# working.net
KiCad netlist of a schematic drawn in EAGLE
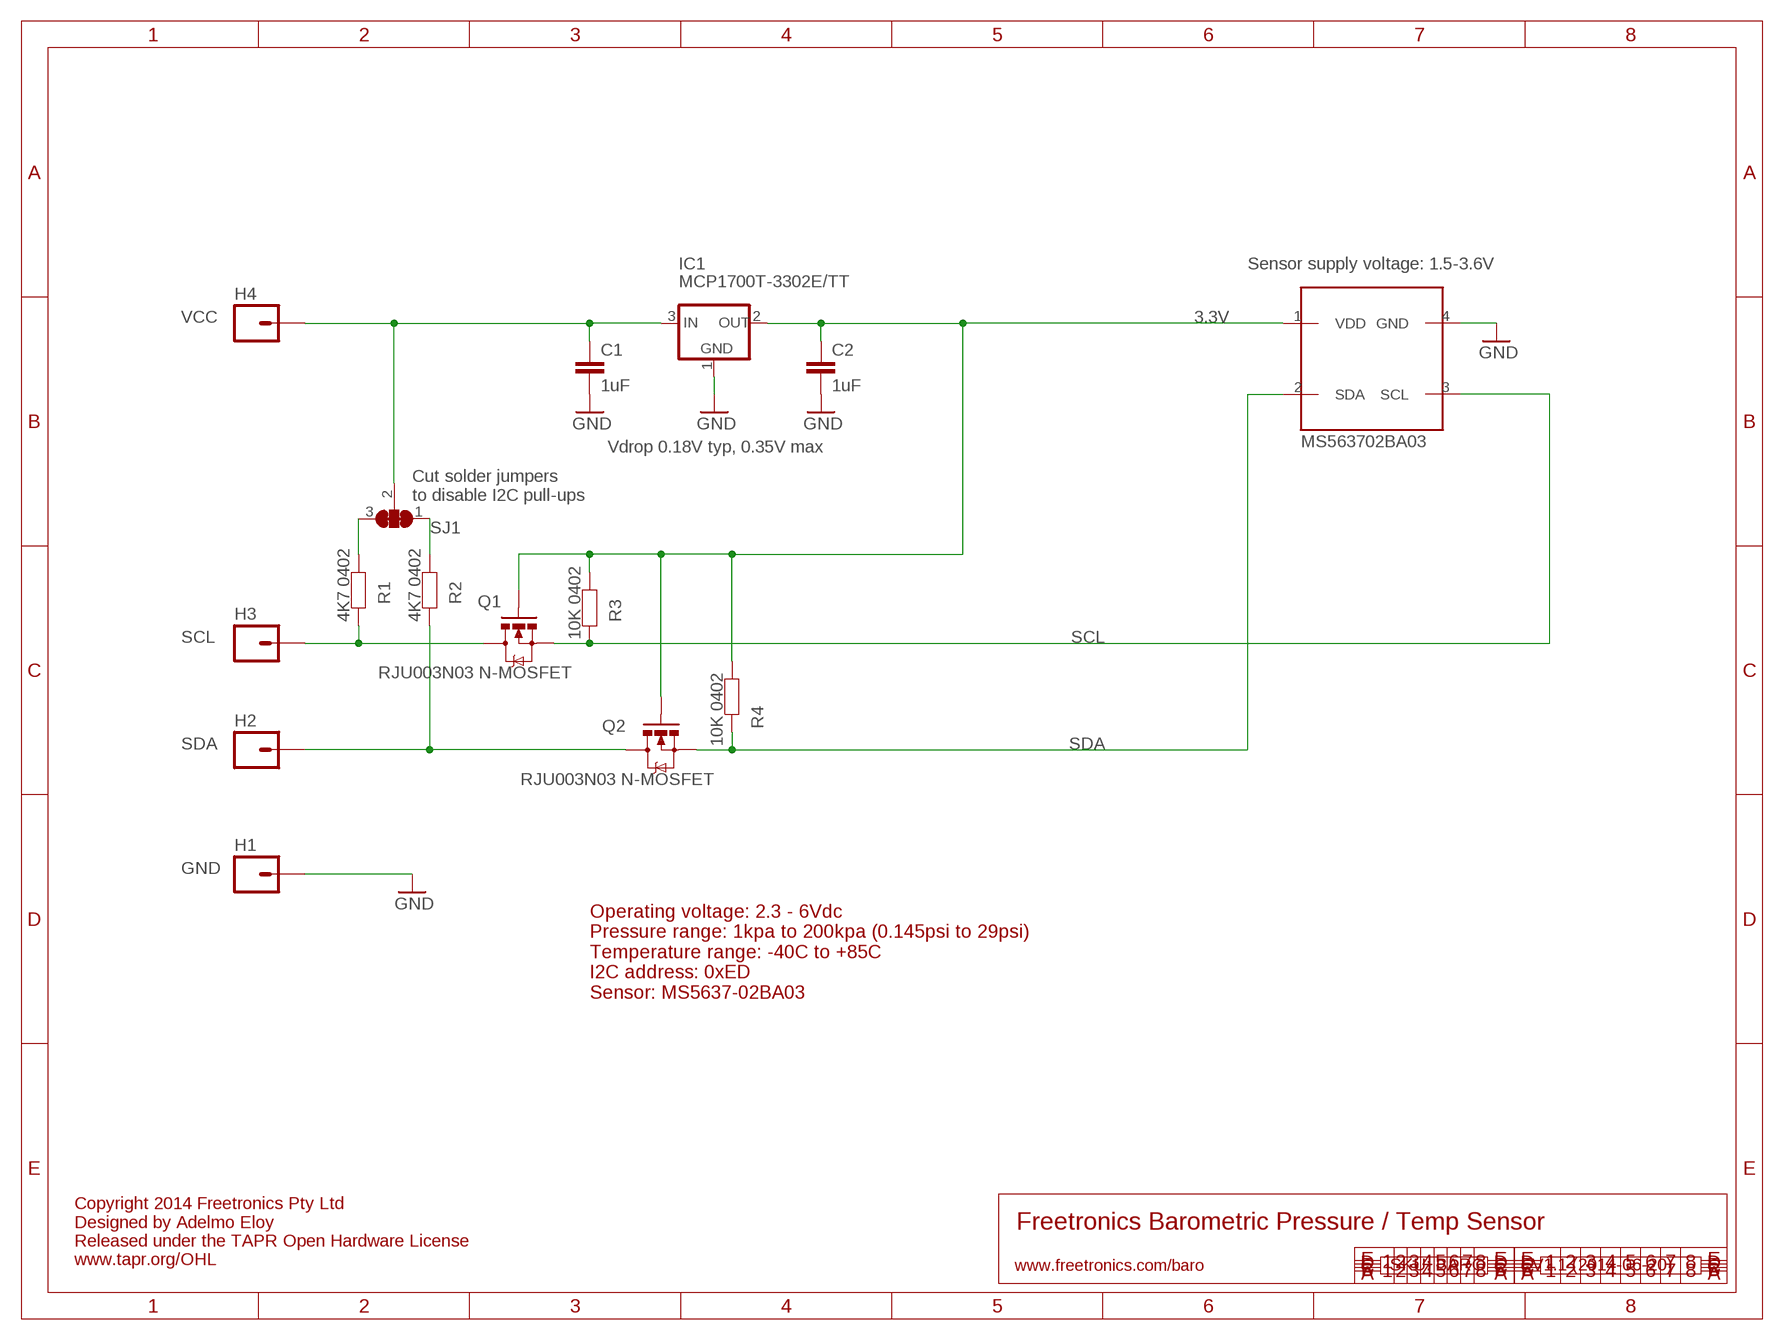
[diagram p0: schematic, sheet 1]

(export (version "E")
  (design (tool "Eeschema 10.0.6"))
  (components
    (comp (ref "C1")
      (value "1uF")
      (footprint "eagle-import:0603")
      (libsource (lib "eagle-import") (part "CAP0603"))
    )
    (comp (ref "C2")
      (value "1uF")
      (footprint "eagle-import:0603")
      (libsource (lib "eagle-import") (part "CAP0603"))
    )
    (comp (ref "H1")
      (value "GND")
      (footprint "eagle-import:1X01")
      (libsource (lib "eagle-import") (part "M01PTH"))
    )
    (comp (ref "H2")
      (value "SDA")
      (footprint "eagle-import:1X01")
      (libsource (lib "eagle-import") (part "M01PTH"))
    )
    (comp (ref "H3")
      (value "SCL")
      (footprint "eagle-import:1X01")
      (libsource (lib "eagle-import") (part "M01PTH"))
    )
    (comp (ref "H4")
      (value "VCC")
      (footprint "eagle-import:1X01")
      (libsource (lib "eagle-import") (part "M01PTH"))
    )
    (comp (ref "IC1")
      (value "MCP1700T-3302E/TT")
      (footprint "eagle-import:SOT23-3")
      (libsource (lib "eagle-import") (part "V_REG_78XXSOT23-3"))
    )
    (comp (ref "IC2")
      (value "MS563702BA03")
      (footprint "eagle-import:MS5637")
      (libsource (lib "eagle-import") (part "MS563702BA03"))
    )
    (comp (ref "Q1")
      (value "RJU003N03 N-MOSFET")
      (footprint "eagle-import:SOT32-3")
      (libsource (lib "eagle-import") (part "MOSFET-NSOT-323"))
    )
    (comp (ref "Q2")
      (value "RJU003N03 N-MOSFET")
      (footprint "eagle-import:SOT32-3")
      (libsource (lib "eagle-import") (part "MOSFET-NSOT-323"))
    )
    (comp (ref "R1")
      (value "4K7 0402")
      (footprint "eagle-import:0402")
      (libsource (lib "eagle-import") (part "RESISTOR0402"))
    )
    (comp (ref "R2")
      (value "4K7 0402")
      (footprint "eagle-import:0402")
      (libsource (lib "eagle-import") (part "RESISTOR0402"))
    )
    (comp (ref "R3")
      (value "10K 0402")
      (footprint "eagle-import:0402")
      (libsource (lib "eagle-import") (part "RESISTOR0402"))
    )
    (comp (ref "R4")
      (value "10K 0402")
      (footprint "eagle-import:0402")
      (libsource (lib "eagle-import") (part "RESISTOR0402"))
    )
    (comp (ref "SJ1")
      (value "SJ2W")
      (footprint "eagle-import:SJ_2")
      (libsource (lib "eagle-import") (part "SJ2W"))
    )
  )
  (nets
    (net (code "1") (name "/3.3V") (class "Default")
      (node (ref "C2") (pin "1") (pinfunction "1_1") (pintype "passive"))
      (node (ref "IC1") (pin "2") (pinfunction "OUT_2") (pintype "output"))
      (node (ref "IC2") (pin "1") (pinfunction "VDD_1") (pintype "bidirectional"))
      (node (ref "Q1") (pin "1") (pinfunction "G_1") (pintype "passive"))
      (node (ref "Q2") (pin "1") (pinfunction "G_1") (pintype "passive"))
      (node (ref "R3") (pin "2") (pinfunction "2_2") (pintype "passive"))
      (node (ref "R4") (pin "2") (pinfunction "2_2") (pintype "passive"))
    )
    (net (code "2") (name "/SCL") (class "Default")
      (node (ref "H3") (pin "1") (pinfunction "1_1") (pintype "passive"))
      (node (ref "Q1") (pin "3") (pinfunction "D_3") (pintype "passive"))
      (node (ref "R1") (pin "1") (pinfunction "1_1") (pintype "passive"))
    )
    (net (code "3") (name "/SDA") (class "Default")
      (node (ref "H2") (pin "1") (pinfunction "1_1") (pintype "passive"))
      (node (ref "Q2") (pin "3") (pinfunction "D_3") (pintype "passive"))
      (node (ref "R2") (pin "1") (pinfunction "1_1") (pintype "passive"))
    )
    (net (code "4") (name "GND") (class "Default")
      (node (ref "C1") (pin "2") (pinfunction "2_2") (pintype "passive"))
      (node (ref "C2") (pin "2") (pinfunction "2_2") (pintype "passive"))
      (node (ref "H1") (pin "1") (pinfunction "1_1") (pintype "passive"))
      (node (ref "IC1") (pin "1") (pinfunction "GND_1") (pintype "input"))
      (node (ref "IC2") (pin "4") (pinfunction "GND_4") (pintype "bidirectional"))
    )
    (net (code "5") (name "Net-(IC1-IN)") (class "Default")
      (node (ref "C1") (pin "1") (pinfunction "1_1") (pintype "passive"))
      (node (ref "H4") (pin "1") (pinfunction "1_1") (pintype "passive"))
      (node (ref "IC1") (pin "3") (pinfunction "IN_3") (pintype "input"))
      (node (ref "SJ1") (pin "2") (pinfunction "2_2") (pintype "passive"))
    )
    (net (code "6") (name "Net-(IC2-SCL)") (class "Default")
      (node (ref "IC2") (pin "3") (pinfunction "SCL_3") (pintype "bidirectional"))
      (node (ref "Q1") (pin "2") (pinfunction "S_2") (pintype "passive"))
      (node (ref "R3") (pin "1") (pinfunction "1_1") (pintype "passive"))
    )
    (net (code "7") (name "Net-(IC2-SDA)") (class "Default")
      (node (ref "IC2") (pin "2") (pinfunction "SDA_2") (pintype "bidirectional"))
      (node (ref "Q2") (pin "2") (pinfunction "S_2") (pintype "passive"))
      (node (ref "R4") (pin "1") (pinfunction "1_1") (pintype "passive"))
    )
    (net (code "8") (name "Net-(R1-Pad2)") (class "Default")
      (node (ref "R1") (pin "2") (pinfunction "2_2") (pintype "passive"))
      (node (ref "SJ1") (pin "3") (pinfunction "3_3") (pintype "passive"))
    )
    (net (code "9") (name "Net-(R2-Pad2)") (class "Default")
      (node (ref "R2") (pin "2") (pinfunction "2_2") (pintype "passive"))
      (node (ref "SJ1") (pin "1") (pinfunction "1_1") (pintype "passive"))
    )
  )
)
